# backplane.net
KiCad netlist of a schematic drawn in EAGLE
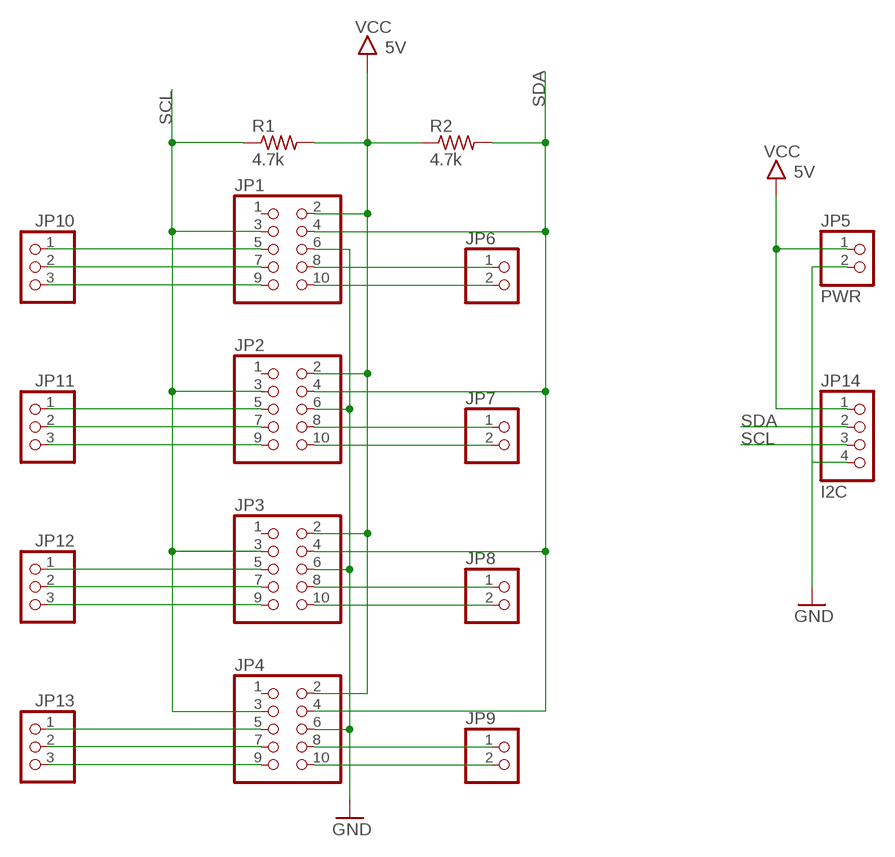
[diagram p0: schematic, sheet 1]

(export (version "E")
  (design (tool "Eeschema 10.0.6"))
  (components
    (comp (ref "JP1")
      (value "PINHD-2X5")
      (footprint "eagle-import:2X05")
      (libsource (lib "eagle-import") (part "PINHD-2X5"))
    )
    (comp (ref "JP2")
      (value "PINHD-2X5")
      (footprint "eagle-import:2X05")
      (libsource (lib "eagle-import") (part "PINHD-2X5"))
    )
    (comp (ref "JP3")
      (value "PINHD-2X5")
      (footprint "eagle-import:2X05")
      (libsource (lib "eagle-import") (part "PINHD-2X5"))
    )
    (comp (ref "JP4")
      (value "PINHD-2X5")
      (footprint "eagle-import:2X05")
      (libsource (lib "eagle-import") (part "PINHD-2X5"))
    )
    (comp (ref "JP5")
      (value "PWR")
      (footprint "eagle-import:1X02-S")
      (libsource (lib "eagle-import") (part "PINHD-1X02_2.54-S"))
    )
    (comp (ref "JP6")
      (value "PINHD-1X02_2.54-S")
      (footprint "eagle-import:1X02-S")
      (libsource (lib "eagle-import") (part "PINHD-1X02_2.54-S"))
    )
    (comp (ref "JP7")
      (value "PINHD-1X02_2.54-S")
      (footprint "eagle-import:1X02-S")
      (libsource (lib "eagle-import") (part "PINHD-1X02_2.54-S"))
    )
    (comp (ref "JP8")
      (value "PINHD-1X02_2.54-S")
      (footprint "eagle-import:1X02-S")
      (libsource (lib "eagle-import") (part "PINHD-1X02_2.54-S"))
    )
    (comp (ref "JP9")
      (value "PINHD-1X02_2.54-S")
      (footprint "eagle-import:1X02-S")
      (libsource (lib "eagle-import") (part "PINHD-1X02_2.54-S"))
    )
    (comp (ref "JP10")
      (value "PINHD-1X03_2.54-S")
      (footprint "eagle-import:1X03-S")
      (libsource (lib "eagle-import") (part "PINHD-1X03_2.54-S"))
    )
    (comp (ref "JP11")
      (value "PINHD-1X03_2.54-S")
      (footprint "eagle-import:1X03-S")
      (libsource (lib "eagle-import") (part "PINHD-1X03_2.54-S"))
    )
    (comp (ref "JP12")
      (value "PINHD-1X03_2.54-S")
      (footprint "eagle-import:1X03-S")
      (libsource (lib "eagle-import") (part "PINHD-1X03_2.54-S"))
    )
    (comp (ref "JP13")
      (value "PINHD-1X03_2.54-S")
      (footprint "eagle-import:1X03-S")
      (libsource (lib "eagle-import") (part "PINHD-1X03_2.54-S"))
    )
    (comp (ref "JP14")
      (value "I2C")
      (footprint "eagle-import:1X04-S")
      (libsource (lib "eagle-import") (part "PINHD-1X04_2.54-S"))
    )
    (comp (ref "R1")
      (value "4.7k")
      (footprint "eagle-import:R0603")
      (libsource (lib "eagle-import") (part "R-US_R0603"))
    )
    (comp (ref "R2")
      (value "4.7k")
      (footprint "eagle-import:R0603")
      (libsource (lib "eagle-import") (part "R-US_R0603"))
    )
  )
  (nets
    (net (code "1") (name "/SCL") (class "Default")
      (node (ref "JP1") (pin "3") (pinfunction "3_3") (pintype "passive"))
      (node (ref "JP14") (pin "3") (pinfunction "3_3") (pintype "passive"))
      (node (ref "JP2") (pin "3") (pinfunction "3_3") (pintype "passive"))
      (node (ref "JP3") (pin "3") (pinfunction "3_3") (pintype "passive"))
      (node (ref "JP4") (pin "3") (pinfunction "3_3") (pintype "passive"))
      (node (ref "R1") (pin "1") (pinfunction "1_1") (pintype "passive"))
    )
    (net (code "2") (name "/SDA") (class "Default")
      (node (ref "JP1") (pin "4") (pinfunction "4_4") (pintype "passive"))
      (node (ref "JP14") (pin "2") (pinfunction "2_2") (pintype "passive"))
      (node (ref "JP2") (pin "4") (pinfunction "4_4") (pintype "passive"))
      (node (ref "JP3") (pin "4") (pinfunction "4_4") (pintype "passive"))
      (node (ref "JP4") (pin "4") (pinfunction "4_4") (pintype "passive"))
      (node (ref "R2") (pin "2") (pinfunction "2_2") (pintype "passive"))
    )
    (net (code "3") (name "5V") (class "Default")
      (node (ref "JP1") (pin "2") (pinfunction "2_2") (pintype "passive"))
      (node (ref "JP14") (pin "1") (pinfunction "1_1") (pintype "passive"))
      (node (ref "JP2") (pin "2") (pinfunction "2_2") (pintype "passive"))
      (node (ref "JP3") (pin "2") (pinfunction "2_2") (pintype "passive"))
      (node (ref "JP4") (pin "2") (pinfunction "2_2") (pintype "passive"))
      (node (ref "JP5") (pin "1") (pinfunction "1_1") (pintype "passive"))
      (node (ref "R1") (pin "2") (pinfunction "2_2") (pintype "passive"))
      (node (ref "R2") (pin "1") (pinfunction "1_1") (pintype "passive"))
    )
    (net (code "4") (name "GND") (class "Default")
      (node (ref "JP1") (pin "6") (pinfunction "6_6") (pintype "passive"))
      (node (ref "JP14") (pin "4") (pinfunction "4_4") (pintype "passive"))
      (node (ref "JP2") (pin "6") (pinfunction "6_6") (pintype "passive"))
      (node (ref "JP3") (pin "6") (pinfunction "6_6") (pintype "passive"))
      (node (ref "JP4") (pin "6") (pinfunction "6_6") (pintype "passive"))
      (node (ref "JP5") (pin "2") (pinfunction "2_2") (pintype "passive"))
    )
    (net (code "5") (name "Net-(JP1-Pad5)") (class "Default")
      (node (ref "JP1") (pin "5") (pinfunction "5_5") (pintype "passive"))
      (node (ref "JP10") (pin "1") (pinfunction "1_1") (pintype "passive"))
    )
    (net (code "6") (name "Net-(JP1-Pad7)") (class "Default")
      (node (ref "JP1") (pin "7") (pinfunction "7_7") (pintype "passive"))
      (node (ref "JP10") (pin "2") (pinfunction "2_2") (pintype "passive"))
    )
    (net (code "7") (name "Net-(JP1-Pad8)") (class "Default")
      (node (ref "JP1") (pin "8") (pinfunction "8_8") (pintype "passive"))
      (node (ref "JP6") (pin "1") (pinfunction "1_1") (pintype "passive"))
    )
    (net (code "8") (name "Net-(JP1-Pad9)") (class "Default")
      (node (ref "JP1") (pin "9") (pinfunction "9_9") (pintype "passive"))
      (node (ref "JP10") (pin "3") (pinfunction "3_3") (pintype "passive"))
    )
    (net (code "9") (name "Net-(JP1-Pad10)") (class "Default")
      (node (ref "JP1") (pin "10") (pinfunction "10_10") (pintype "passive"))
      (node (ref "JP6") (pin "2") (pinfunction "2_2") (pintype "passive"))
    )
    (net (code "10") (name "Net-(JP2-Pad8)") (class "Default")
      (node (ref "JP2") (pin "8") (pinfunction "8_8") (pintype "passive"))
      (node (ref "JP7") (pin "1") (pinfunction "1_1") (pintype "passive"))
    )
    (net (code "11") (name "Net-(JP2-Pad10)") (class "Default")
      (node (ref "JP2") (pin "10") (pinfunction "10_10") (pintype "passive"))
      (node (ref "JP7") (pin "2") (pinfunction "2_2") (pintype "passive"))
    )
    (net (code "12") (name "Net-(JP3-Pad8)") (class "Default")
      (node (ref "JP3") (pin "8") (pinfunction "8_8") (pintype "passive"))
      (node (ref "JP8") (pin "1") (pinfunction "1_1") (pintype "passive"))
    )
    (net (code "13") (name "Net-(JP3-Pad10)") (class "Default")
      (node (ref "JP3") (pin "10") (pinfunction "10_10") (pintype "passive"))
      (node (ref "JP8") (pin "2") (pinfunction "2_2") (pintype "passive"))
    )
    (net (code "14") (name "Net-(JP4-Pad8)") (class "Default")
      (node (ref "JP4") (pin "8") (pinfunction "8_8") (pintype "passive"))
      (node (ref "JP9") (pin "1") (pinfunction "1_1") (pintype "passive"))
    )
    (net (code "15") (name "Net-(JP4-Pad10)") (class "Default")
      (node (ref "JP4") (pin "10") (pinfunction "10_10") (pintype "passive"))
      (node (ref "JP9") (pin "2") (pinfunction "2_2") (pintype "passive"))
    )
    (net (code "16") (name "Net-(JP11-Pad1)") (class "Default")
      (node (ref "JP11") (pin "1") (pinfunction "1_1") (pintype "passive"))
      (node (ref "JP2") (pin "5") (pinfunction "5_5") (pintype "passive"))
    )
    (net (code "17") (name "Net-(JP11-Pad2)") (class "Default")
      (node (ref "JP11") (pin "2") (pinfunction "2_2") (pintype "passive"))
      (node (ref "JP2") (pin "7") (pinfunction "7_7") (pintype "passive"))
    )
    (net (code "18") (name "Net-(JP11-Pad3)") (class "Default")
      (node (ref "JP11") (pin "3") (pinfunction "3_3") (pintype "passive"))
      (node (ref "JP2") (pin "9") (pinfunction "9_9") (pintype "passive"))
    )
    (net (code "19") (name "Net-(JP12-Pad1)") (class "Default")
      (node (ref "JP12") (pin "1") (pinfunction "1_1") (pintype "passive"))
      (node (ref "JP3") (pin "5") (pinfunction "5_5") (pintype "passive"))
    )
    (net (code "20") (name "Net-(JP12-Pad2)") (class "Default")
      (node (ref "JP12") (pin "2") (pinfunction "2_2") (pintype "passive"))
      (node (ref "JP3") (pin "7") (pinfunction "7_7") (pintype "passive"))
    )
    (net (code "21") (name "Net-(JP12-Pad3)") (class "Default")
      (node (ref "JP12") (pin "3") (pinfunction "3_3") (pintype "passive"))
      (node (ref "JP3") (pin "9") (pinfunction "9_9") (pintype "passive"))
    )
    (net (code "22") (name "Net-(JP13-Pad1)") (class "Default")
      (node (ref "JP13") (pin "1") (pinfunction "1_1") (pintype "passive"))
      (node (ref "JP4") (pin "5") (pinfunction "5_5") (pintype "passive"))
    )
    (net (code "23") (name "Net-(JP13-Pad2)") (class "Default")
      (node (ref "JP13") (pin "2") (pinfunction "2_2") (pintype "passive"))
      (node (ref "JP4") (pin "7") (pinfunction "7_7") (pintype "passive"))
    )
    (net (code "24") (name "Net-(JP13-Pad3)") (class "Default")
      (node (ref "JP13") (pin "3") (pinfunction "3_3") (pintype "passive"))
      (node (ref "JP4") (pin "9") (pinfunction "9_9") (pintype "passive"))
    )
    (net (code "25") (name "unconnected-(JP1-Pad1)") (class "Default")
      (node (ref "JP1") (pin "1") (pinfunction "1_1") (pintype "passive"))
    )
    (net (code "26") (name "unconnected-(JP2-Pad1)") (class "Default")
      (node (ref "JP2") (pin "1") (pinfunction "1_1") (pintype "passive"))
    )
    (net (code "27") (name "unconnected-(JP3-Pad1)") (class "Default")
      (node (ref "JP3") (pin "1") (pinfunction "1_1") (pintype "passive"))
    )
    (net (code "28") (name "unconnected-(JP4-Pad1)") (class "Default")
      (node (ref "JP4") (pin "1") (pinfunction "1_1") (pintype "passive"))
    )
  )
)
